# Cascade.net
KiCad netlist of a schematic drawn in Altium Designer
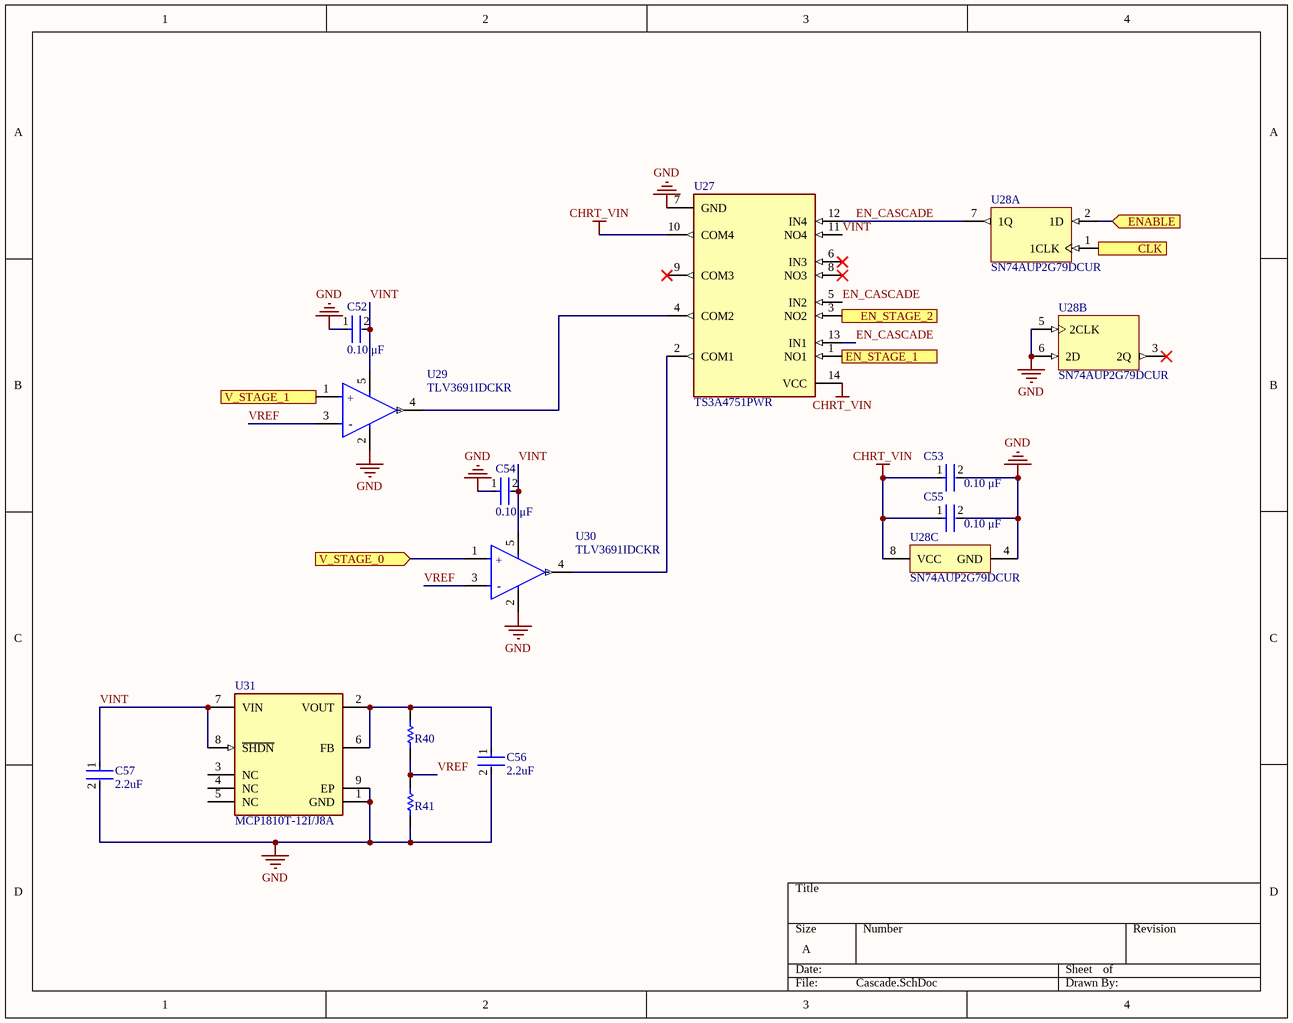
[diagram p0: Cascade.SchDoc]

(export (version "E")
  (design (tool "Eeschema 10.0.6"))
  (components
    (comp (ref "C52")
      (value "C0402C104K8PACTU")
      (footprint "FP-C0402-BB-MFG")
      (description "CAP CER 0.1UF 10V X5R 0402")
      (fields
        (field (name "CAPACITANCE") "0.10 μF")
        (field (name "MANUFACTURER") "Kemet")
        (field (name "TOLERANCE") "0.1")
      )
      (libsource (lib "Altium Content Vault") (part "b4654b650e69147ec39a6b967a45e02"))
    )
    (comp (ref "C53")
      (value "C0402C104K8PACTU")
      (footprint "FP-C0402-BB-MFG")
      (description "CAP CER 0.1UF 10V X5R 0402")
      (fields
        (field (name "CAPACITANCE") "0.10 μF")
        (field (name "MANUFACTURER") "Kemet")
        (field (name "TOLERANCE") "0.1")
      )
      (libsource (lib "Altium Content Vault") (part "b4654b650e69147ec39a6b967a45e02"))
    )
    (comp (ref "C54")
      (value "C0402C104K8PACTU")
      (footprint "FP-C0402-BB-MFG")
      (description "CAP CER 0.1UF 10V X5R 0402")
      (fields
        (field (name "CAPACITANCE") "0.10 μF")
        (field (name "MANUFACTURER") "Kemet")
        (field (name "TOLERANCE") "0.1")
      )
      (libsource (lib "Altium Content Vault") (part "b4654b650e69147ec39a6b967a45e02"))
    )
    (comp (ref "C55")
      (value "C0402C104K8PACTU")
      (footprint "FP-C0402-BB-MFG")
      (description "CAP CER 0.1UF 10V X5R 0402")
      (fields
        (field (name "CAPACITANCE") "0.10 μF")
        (field (name "MANUFACTURER") "Kemet")
        (field (name "TOLERANCE") "0.1")
      )
      (libsource (lib "Altium Content Vault") (part "b4654b650e69147ec39a6b967a45e02"))
    )
    (comp (ref "C56")
      (value "GRM188R71A225KE15D")
      (footprint "FP-GRM188-0_1-e0_2_0_5-MFG")
      (description "Chip Multilayer Ceramic Capacitors for General Purpose, 0603, 2.2uF, X7R, 15%, 10%, 10V")
      (fields
        (field (name "VOLTAGE") "10V")
        (field (name "CAPACITANCE") "2.2uF")
        (field (name "TOLERANCE") "10%")
      )
      (libsource (lib "Altium Content Vault") (part "11868f565c42a9108669ba33697ecf6"))
    )
    (comp (ref "C57")
      (value "GRM188R71A225KE15D")
      (footprint "FP-GRM188-0_1-e0_2_0_5-MFG")
      (description "Chip Multilayer Ceramic Capacitors for General Purpose, 0603, 2.2uF, X7R, 15%, 10%, 10V")
      (fields
        (field (name "VOLTAGE") "10V")
        (field (name "CAPACITANCE") "2.2uF")
        (field (name "TOLERANCE") "10%")
      )
      (libsource (lib "Altium Content Vault") (part "11868f565c42a9108669ba33697ecf6"))
    )
    (comp (ref "R40")
      (value "ERJ-2GEJ915X")
      (footprint "RESC1005X40X25LL05T05")
      (fields (field (name "MANUFACTURER") "Panasonic"))
      (libsource (lib "Altium Content Vault") (part "RES"))
    )
    (comp (ref "R41")
      (value "CRCW04022M40FKED")
      (footprint "RESC1005X40X25LL05T05")
      (fields (field (name "MANUFACTURER") "Vishay Dale"))
      (libsource (lib "Altium Content Vault") (part "RES"))
    )
    (comp (ref "U27")
      (value "TS3A4751PWR")
      (footprint "FP-PW0014A-IPC_C")
      (description "IC SWITCH QUAD SPST 14TSSOP")
      (libsource (lib "Altium Content Vault") (part "75fdcfb842d41a92b92a478e82e68ae"))
    )
    (comp (ref "U28")
      (value "SN74AUP2G79DCUR")
      (footprint "DCU0008A_L")
      (description "Low-Power Dual Positive-Edge-Triggered D-Type Flip-Flop, DCU0008A, LARGE T&R")
      (fields
        (field (name "MANUFACTURER") "Texas Instruments")
        (field (name "GENERIC PART NUMBER") "SN74AUP2G79")
      )
      (libsource (lib "") (part "TI-SN74XXX2G79-8_A_1"))
    )
    (comp (ref "U29")
      (value "TLV3691IDCKR")
      (footprint "FP-DCK0005A-IPC_A")
      (description "IC COMPARATOR NANO-POWER SC70-5")
      (libsource (lib "Altium Content Vault") (part "3dae5d43319efa9f60be5f7de20330d"))
    )
    (comp (ref "U30")
      (value "TLV3691IDCKR")
      (footprint "FP-DCK0005A-IPC_A")
      (description "IC COMPARATOR NANO-POWER SC70-5")
      (libsource (lib "Altium Content Vault") (part "3dae5d43319efa9f60be5f7de20330d"))
    )
    (comp (ref "U31")
      (value "MCP1810T-12I/J8A")
      (footprint "FP-C04-1207A-MFG")
      (description "IC REG LINEAR 1.2V 150MA 8VDFN")
      (fields
        (field (name "MANUFACTURER") "Microchip Technology")
        (field (name "OCTOPART") "https://octopart.com/mcp1810t-12i%2Fj8a-microchip-75615047")
      )
      (libsource (lib "Altium Content Vault") (part "9c464f695c2e69d33b93af79e311a43"))
    )
  )
  (nets
    (net (code "1") (name "/CLK") (class "Default")
      (node (ref "U28") (pin "1") (pinfunction "1CLK_1") (pintype "input"))
    )
    (net (code "2") (name "/ENABLE") (class "Default")
      (node (ref "U28") (pin "2") (pinfunction "1D_2") (pintype "input"))
    )
    (net (code "3") (name "/EN_CASCADE") (class "Default")
      (node (ref "U27") (pin "12") (pinfunction "IN4_12") (pintype "input"))
      (node (ref "U27") (pin "13") (pinfunction "IN1_13") (pintype "input"))
      (node (ref "U27") (pin "5") (pinfunction "IN2_5") (pintype "input"))
      (node (ref "U28") (pin "7") (pinfunction "1Q_7") (pintype "output"))
    )
    (net (code "4") (name "/EN_STAGE_1") (class "Default")
      (node (ref "U27") (pin "1") (pinfunction "NO1_1") (pintype "input"))
    )
    (net (code "5") (name "/EN_STAGE_2") (class "Default")
      (node (ref "U27") (pin "3") (pinfunction "NO2_3") (pintype "input"))
    )
    (net (code "6") (name "/VINT") (class "Default")
      (node (ref "C52") (pin "2") (pinfunction "2_2") (pintype "passive"))
      (node (ref "C54") (pin "2") (pinfunction "2_2") (pintype "passive"))
      (node (ref "C57") (pin "1") (pinfunction "1_1") (pintype "passive"))
      (node (ref "U27") (pin "11") (pinfunction "NO4_11") (pintype "input"))
      (node (ref "U29") (pin "5") (pinfunction "VCC_5") (pintype "power_in"))
      (node (ref "U30") (pin "5") (pinfunction "VCC_5") (pintype "power_in"))
      (node (ref "U31") (pin "7") (pinfunction "VIN_7") (pintype "power_in"))
      (node (ref "U31") (pin "8") (pinfunction "~{SHDN}_8") (pintype "input"))
    )
    (net (code "7") (name "/VREF") (class "Default")
      (node (ref "R40") (pin "1") (pinfunction "1_1") (pintype "passive"))
      (node (ref "R41") (pin "1") (pinfunction "1_1") (pintype "passive"))
      (node (ref "U29") (pin "3") (pinfunction "IN-_3") (pintype "tri_state"))
      (node (ref "U30") (pin "3") (pinfunction "IN-_3") (pintype "tri_state"))
    )
    (net (code "8") (name "/V_STAGE_0") (class "Default")
      (node (ref "U30") (pin "1") (pinfunction "IN+_1") (pintype "tri_state"))
    )
    (net (code "9") (name "/V_STAGE_1") (class "Default")
      (node (ref "U29") (pin "1") (pinfunction "IN+_1") (pintype "tri_state"))
    )
    (net (code "10") (name "CHRT_VIN") (class "Default")
      (node (ref "C53") (pin "1") (pinfunction "1_1") (pintype "passive"))
      (node (ref "C55") (pin "1") (pinfunction "1_1") (pintype "passive"))
      (node (ref "U27") (pin "10") (pinfunction "COM4_10") (pintype "output"))
      (node (ref "U27") (pin "14") (pinfunction "VCC_14") (pintype "power_in"))
      (node (ref "U28") (pin "8") (pinfunction "VCC_8") (pintype "power_in"))
    )
    (net (code "11") (name "GND") (class "Default")
      (node (ref "C52") (pin "1") (pinfunction "1_1") (pintype "passive"))
      (node (ref "C53") (pin "2") (pinfunction "2_2") (pintype "passive"))
      (node (ref "C54") (pin "1") (pinfunction "1_1") (pintype "passive"))
      (node (ref "C55") (pin "2") (pinfunction "2_2") (pintype "passive"))
      (node (ref "C56") (pin "2") (pinfunction "2_2") (pintype "passive"))
      (node (ref "C57") (pin "2") (pinfunction "2_2") (pintype "passive"))
      (node (ref "R41") (pin "2") (pinfunction "2_2") (pintype "passive"))
      (node (ref "U27") (pin "7") (pinfunction "GND_7") (pintype "power_in"))
      (node (ref "U28") (pin "4") (pinfunction "GND_4") (pintype "power_in"))
      (node (ref "U28") (pin "5") (pinfunction "2CLK_5") (pintype "input"))
      (node (ref "U28") (pin "6") (pinfunction "2D_6") (pintype "input"))
      (node (ref "U29") (pin "2") (pinfunction "GND_2") (pintype "power_in"))
      (node (ref "U30") (pin "2") (pinfunction "GND_2") (pintype "power_in"))
      (node (ref "U31") (pin "1") (pinfunction "GND_1") (pintype "power_in"))
      (node (ref "U31") (pin "9") (pinfunction "EP_9") (pintype "power_in"))
    )
    (net (code "12") (name "Net-(U27-COM1)") (class "Default")
      (node (ref "U27") (pin "2") (pinfunction "COM1_2") (pintype "output"))
      (node (ref "U30") (pin "4") (pinfunction "OUT_4") (pintype "output"))
    )
    (net (code "13") (name "Net-(U27-COM2)") (class "Default")
      (node (ref "U27") (pin "4") (pinfunction "COM2_4") (pintype "output"))
      (node (ref "U29") (pin "4") (pinfunction "OUT_4") (pintype "output"))
    )
    (net (code "14") (name "Net-(U31-FB)") (class "Default")
      (node (ref "C56") (pin "1") (pinfunction "1_1") (pintype "passive"))
      (node (ref "R40") (pin "2") (pinfunction "2_2") (pintype "passive"))
      (node (ref "U31") (pin "2") (pinfunction "VOUT_2") (pintype "power_in"))
      (node (ref "U31") (pin "6") (pinfunction "FB_6") (pintype "passive"))
    )
    (net (code "15") (name "unconnected-(U27-COM3-Pad9)") (class "Default")
      (node (ref "U27") (pin "9") (pinfunction "COM3_9") (pintype "output+no_connect"))
    )
    (net (code "16") (name "unconnected-(U27-IN3-Pad6)") (class "Default")
      (node (ref "U27") (pin "6") (pinfunction "IN3_6") (pintype "input+no_connect"))
    )
    (net (code "17") (name "unconnected-(U27-NO3-Pad8)") (class "Default")
      (node (ref "U27") (pin "8") (pinfunction "NO3_8") (pintype "input+no_connect"))
    )
    (net (code "18") (name "unconnected-(U28B-2Q-Pad3)") (class "Default")
      (node (ref "U28") (pin "3") (pinfunction "2Q_3") (pintype "output+no_connect"))
    )
    (net (code "19") (name "unconnected-(U31-NC-Pad3)") (class "Default")
      (node (ref "U31") (pin "3") (pinfunction "NC_3") (pintype "passive"))
    )
    (net (code "20") (name "unconnected-(U31-NC-Pad4)") (class "Default")
      (node (ref "U31") (pin "4") (pinfunction "NC_4") (pintype "passive"))
    )
    (net (code "21") (name "unconnected-(U31-NC-Pad5)") (class "Default")
      (node (ref "U31") (pin "5") (pinfunction "NC_5") (pintype "passive"))
    )
  )
)
